# CopterControl_3D.net
KiCad netlist of a schematic drawn in Altium Designer
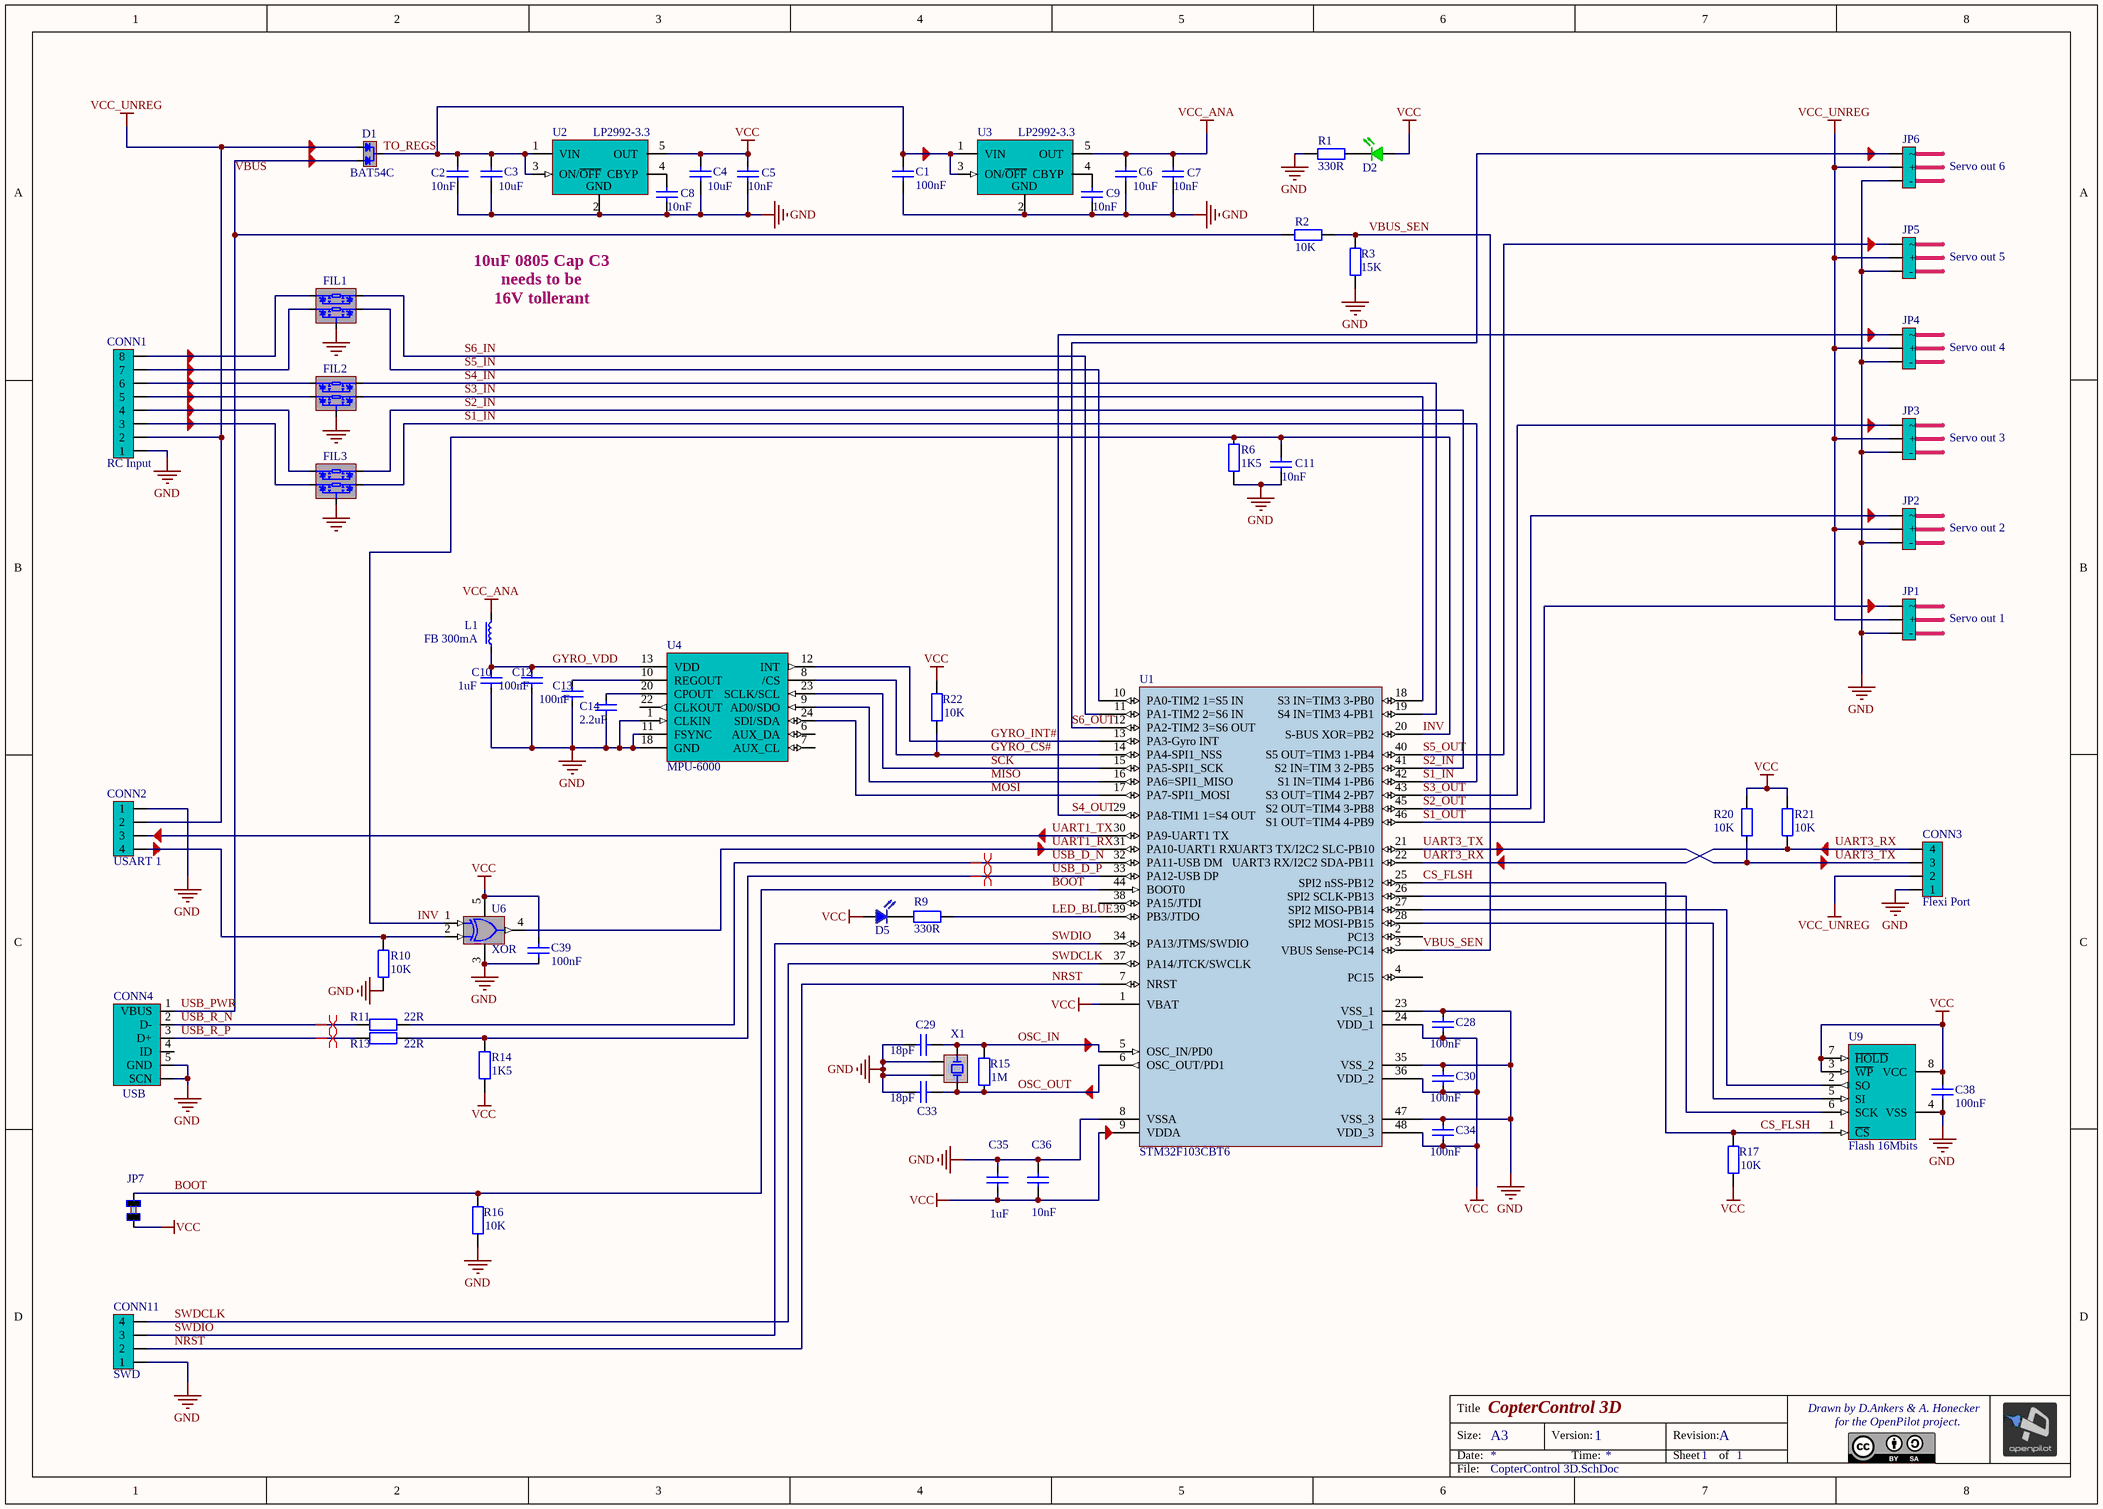
[diagram p0: CopterControl 3D.SchDoc]

(export (version "E")
  (design (tool "Eeschema 10.0.6"))
  (components
    (comp (ref "C1")
      (value "100nF")
      (footprint "CAP603N")
      (description "Capacitor SMD")
      (fields (field (name "Comment") "Cap603") (field (name "PUBLISHER") "The OpenPilot Project"))
      (libsource (lib "OpenPilot") (part "Cap603"))
    )
    (comp (ref "C2")
      (value "10nF")
      (footprint "CAP603L")
      (description "Capacitor SMD")
      (fields (field (name "Comment") "Cap603") (field (name "PUBLISHER") "The OpenPilot Project"))
      (libsource (lib "OpenPilot") (part "Cap603"))
    )
    (comp (ref "C3")
      (value "10uF")
      (footprint "CAP805L")
      (description "Capacitor SMD")
      (fields (field (name "Comment") "Cap805") (field (name "PUBLISHER") "The OpenPilot Project"))
      (libsource (lib "OpenPilot") (part "Cap805"))
    )
    (comp (ref "C4")
      (value "10uF")
      (footprint "CAP805L")
      (description "Capacitor SMD")
      (fields (field (name "Comment") "Cap805") (field (name "PUBLISHER") "The OpenPilot Project"))
      (libsource (lib "OpenPilot") (part "Cap805"))
    )
    (comp (ref "C5")
      (value "10nF")
      (footprint "CAP603N")
      (description "Capacitor SMD")
      (fields (field (name "Comment") "Cap603") (field (name "PUBLISHER") "The OpenPilot Project"))
      (libsource (lib "OpenPilot") (part "Cap603"))
    )
    (comp (ref "C6")
      (value "10uF")
      (footprint "CAP805L")
      (description "Capacitor SMD")
      (fields (field (name "Comment") "Cap805") (field (name "PUBLISHER") "The OpenPilot Project"))
      (libsource (lib "OpenPilot") (part "Cap805"))
    )
    (comp (ref "C7")
      (value "10nF")
      (footprint "CAP603N")
      (description "Capacitor SMD")
      (fields (field (name "Comment") "Cap603") (field (name "PUBLISHER") "The OpenPilot Project"))
      (libsource (lib "OpenPilot") (part "Cap603"))
    )
    (comp (ref "C8")
      (value "10nF")
      (footprint "CAP603N")
      (description "Capacitor SMD")
      (fields (field (name "Comment") "Cap603") (field (name "PUBLISHER") "The OpenPilot Project"))
      (libsource (lib "OpenPilot") (part "Cap603"))
    )
    (comp (ref "C9")
      (value "10nF")
      (footprint "CAP603N")
      (description "Capacitor SMD")
      (fields (field (name "Comment") "Cap603") (field (name "PUBLISHER") "The OpenPilot Project"))
      (libsource (lib "OpenPilot") (part "Cap603"))
    )
    (comp (ref "C10")
      (value "1uF")
      (footprint "CAP603L")
      (description "Capacitor SMD")
      (fields (field (name "Comment") "Cap603") (field (name "PUBLISHER") "The OpenPilot Project"))
      (libsource (lib "") (part "Cap603_1"))
    )
    (comp (ref "C11")
      (value "10nF")
      (footprint "CAP603N")
      (description "Capacitor SMD")
      (fields (field (name "Comment") "Cap603") (field (name "PUBLISHER") "The OpenPilot Project"))
      (libsource (lib "OpenPilot") (part "Cap603"))
    )
    (comp (ref "C12")
      (value "100nF")
      (footprint "CAP603L")
      (description "Capacitor SMD")
      (fields (field (name "Comment") "Cap603") (field (name "PUBLISHER") "The OpenPilot Project"))
      (libsource (lib "") (part "Cap603_1"))
    )
    (comp (ref "C13")
      (value "100nF")
      (footprint "CAP603L")
      (description "Capacitor SMD")
      (fields (field (name "Comment") "Cap603") (field (name "PUBLISHER") "The OpenPilot Project"))
      (libsource (lib "") (part "Cap603_1"))
    )
    (comp (ref "C14")
      (value "2.2uF")
      (footprint "CAP603L")
      (description "Capacitor SMD")
      (fields (field (name "Comment") "Cap603") (field (name "PUBLISHER") "The OpenPilot Project"))
      (libsource (lib "") (part "Cap603_1"))
    )
    (comp (ref "C28")
      (value "100nF")
      (footprint "CAP603N")
      (description "Capacitor SMD")
      (fields (field (name "Comment") "Cap603") (field (name "PUBLISHER") "The OpenPilot Project"))
      (libsource (lib "") (part "Cap603_1"))
    )
    (comp (ref "C29")
      (value "18pF")
      (footprint "CAP603N")
      (description "Capacitor SMD")
      (fields (field (name "Comment") "Cap603") (field (name "PUBLISHER") "The OpenPilot Project"))
      (libsource (lib "OpenPilot") (part "Cap603"))
    )
    (comp (ref "C30")
      (value "100nF")
      (footprint "CAP603N")
      (description "Capacitor SMD")
      (fields (field (name "Comment") "Cap603") (field (name "PUBLISHER") "The OpenPilot Project"))
      (libsource (lib "") (part "Cap603_1"))
    )
    (comp (ref "C33")
      (value "18pF")
      (footprint "CAP603N")
      (description "Capacitor SMD")
      (fields (field (name "Comment") "Cap603") (field (name "PUBLISHER") "The OpenPilot Project"))
      (libsource (lib "OpenPilot") (part "Cap603"))
    )
    (comp (ref "C34")
      (value "100nF")
      (footprint "CAP603N")
      (description "Capacitor SMD")
      (fields (field (name "Comment") "Cap603") (field (name "PUBLISHER") "The OpenPilot Project"))
      (libsource (lib "") (part "Cap603_1"))
    )
    (comp (ref "C35")
      (value "1uF")
      (footprint "CAP603L")
      (description "Capacitor SMD")
      (fields (field (name "Comment") "Cap603") (field (name "PUBLISHER") "The OpenPilot Project"))
      (libsource (lib "") (part "Cap603_1"))
    )
    (comp (ref "C36")
      (value "10nF")
      (footprint "CAP603N")
      (description "Capacitor SMD")
      (fields (field (name "Comment") "Cap603") (field (name "PUBLISHER") "The OpenPilot Project"))
      (libsource (lib "OpenPilot") (part "Cap603"))
    )
    (comp (ref "C38")
      (value "100nF")
      (footprint "CAP603N")
      (description "Capacitor SMD")
      (fields (field (name "Comment") "Cap603") (field (name "PUBLISHER") "The OpenPilot Project"))
      (libsource (lib "OpenPilot") (part "Cap603"))
    )
    (comp (ref "C39")
      (value "100nF")
      (footprint "CAP603N")
      (description "Capacitor SMD")
      (fields (field (name "Comment") "Cap603") (field (name "PUBLISHER") "The OpenPilot Project"))
      (libsource (lib "") (part "Cap603_1"))
    )
    (comp (ref "CONN1")
      (value "RC Input")
      (footprint "JST SH 8 Pin Side Entry")
      (description "JST-SH 8-pin Side Entry Socket")
      (fields (field (name "MANUFACTURER") "Generic Components"))
      (libsource (lib "OpenPilot") (part "JST-SH 8-pin Side Entry Socket"))
    )
    (comp (ref "CONN2")
      (value "USART 1")
      (footprint "JST SH 4 Pin Side Entry")
      (description "JST-SH 4-pin Side Entry Socket")
      (fields (field (name "MANUFACTURER") "Generic Components"))
      (libsource (lib "") (part "JST-SH 4-pin Side Entry Socket_2"))
    )
    (comp (ref "CONN3")
      (value "Flexi Port")
      (footprint "JST SH 4 Pin Side Entry")
      (description "JST-SH 4-pin Side Entry Socket")
      (fields (field (name "MANUFACTURER") "Generic Components"))
      (libsource (lib "OpenPilot") (part "JST-SH 4-pin Side Entry Socket"))
    )
    (comp (ref "CONN4")
      (value "USB")
      (footprint "USB SMD")
      (description "USB Type-B SMT Socket")
      (libsource (lib "OpenPilot") (part "USB_SMT_B"))
    )
    (comp (ref "CONN11")
      (value "SWD")
      (footprint "JST SH 4 Pin Side Entry")
      (description "JST-SH 4-pin Side Entry Socket")
      (fields (field (name "MANUFACTURER") "Generic Components"))
      (libsource (lib "") (part "JST-SH 4-pin Side Entry Socket_1"))
    )
    (comp (ref "D1")
      (value "BAT54C")
      (footprint "SOT23-3N")
      (description "Dual Diode Command Cathode")
      (libsource (lib "OpenPilot") (part "BAT54C"))
    )
    (comp (ref "D2")
      (value "Green")
      (footprint "LED603N")
      (description "Green 603 LED")
      (libsource (lib "OpenPilot") (part "LED 603 Gr"))
    )
    (comp (ref "D5")
      (value "Blue")
      (footprint "LED603N")
      (description "Blue 603 LED")
      (libsource (lib "OpenPilot") (part "LED 603 Bl"))
    )
    (comp (ref "FIL1")
      (value "IP4256CZ5-W,115")
      (footprint "SOT-665")
      (description "IP4256CZ5-W,115 2 channel, 100R, 30pF, RF ESD Filter")
      (fields
        (field (name "MANUFACTURER") "Generic Components")
        (field (name "PUBLISHER") "The OpenPilot Project")
      )
      (libsource (lib "OpenPilot") (part "RF Filter 100R 30pF"))
    )
    (comp (ref "FIL2")
      (value "IP4256CZ5-W,115")
      (footprint "SOT-665")
      (description "IP4256CZ5-W,115 2 channel, 100R, 30pF, RF ESD Filter")
      (fields
        (field (name "MANUFACTURER") "Generic Components")
        (field (name "PUBLISHER") "The OpenPilot Project")
      )
      (libsource (lib "OpenPilot") (part "RF Filter 100R 30pF"))
    )
    (comp (ref "FIL3")
      (value "IP4256CZ5-W,115")
      (footprint "SOT-665")
      (description "IP4256CZ5-W,115 2 channel, 100R, 30pF, RF ESD Filter")
      (fields
        (field (name "MANUFACTURER") "Generic Components")
        (field (name "PUBLISHER") "The OpenPilot Project")
      )
      (libsource (lib "OpenPilot") (part "RF Filter 100R 30pF"))
    )
    (comp (ref "JP1")
      (value "Servo out 1")
      (footprint "SIP3 - 0.1")
      (description "Header, 3-Pin, 0.1\"")
      (fields (field (name "MANUFACTURER") "Generic Components"))
      (libsource (lib "OpenPilot") (part "Hdr 3 Pin 0.1"))
    )
    (comp (ref "JP2")
      (value "Servo out 2")
      (footprint "SIP3 - 0.1")
      (description "Header, 3-Pin, 0.1\"")
      (fields (field (name "MANUFACTURER") "Generic Components"))
      (libsource (lib "OpenPilot") (part "Hdr 3 Pin 0.1"))
    )
    (comp (ref "JP3")
      (value "Servo out 3")
      (footprint "SIP3 - 0.1")
      (description "Header, 3-Pin, 0.1\"")
      (fields (field (name "MANUFACTURER") "Generic Components"))
      (libsource (lib "OpenPilot") (part "Hdr 3 Pin 0.1"))
    )
    (comp (ref "JP4")
      (value "Servo out 4")
      (footprint "SIP3 - 0.1")
      (description "Header, 3-Pin, 0.1\"")
      (fields (field (name "MANUFACTURER") "Generic Components"))
      (libsource (lib "OpenPilot") (part "Hdr 3 Pin 0.1"))
    )
    (comp (ref "JP5")
      (value "Servo out 5")
      (footprint "SIP3 - 0.1")
      (description "Header, 3-Pin, 0.1\"")
      (fields (field (name "MANUFACTURER") "Generic Components"))
      (libsource (lib "OpenPilot") (part "Hdr 3 Pin 0.1"))
    )
    (comp (ref "JP6")
      (value "Servo out 6")
      (footprint "SIP3 - 0.1")
      (description "Header, 3-Pin, 0.1\"")
      (fields (field (name "MANUFACTURER") "Generic Components"))
      (libsource (lib "OpenPilot") (part "Hdr 3 Pin 0.1"))
    )
    (comp (ref "JP7")
      (value "2 PAD Touch JMP")
      (footprint "TOUCH JMP 2PAD")
      (description "2 Pad Touch Jumper")
      (fields (field (name "PUBLISHER") "The OpenPilot Project"))
      (libsource (lib "OpenPilot") (part "2 PAD Touch JMP"))
    )
    (comp (ref "L1")
      (value "FB 300mA")
      (footprint "IND603N")
      (description "Ferrite Bead 300mA")
      (fields (field (name "MANUFACTURER") "Generic Components"))
      (libsource (lib "OpenPilot") (part "FerriteBead_300mA"))
    )
    (comp (ref "R1")
      (value "330R")
      (footprint "RES603N")
      (description "Resistor SMD")
      (fields (field (name "Comment") "Res603") (field (name "PUBLISHER") "The OpenPilot Project"))
      (libsource (lib "") (part "Res603_1"))
    )
    (comp (ref "R2")
      (value "10K")
      (footprint "RES603N")
      (description "Resistor SMD")
      (fields (field (name "Comment") "Res603") (field (name "PUBLISHER") "The OpenPilot Project"))
      (libsource (lib "") (part "Res603_1"))
    )
    (comp (ref "R3")
      (value "15K")
      (footprint "RES603N")
      (description "Resistor SMD")
      (fields (field (name "Comment") "Res603") (field (name "PUBLISHER") "The OpenPilot Project"))
      (libsource (lib "OpenPilot") (part "Res603"))
    )
    (comp (ref "R6")
      (value "1K5")
      (footprint "RES603N")
      (description "Resistor SMD")
      (fields (field (name "Comment") "Res603") (field (name "PUBLISHER") "The OpenPilot Project"))
      (libsource (lib "") (part "Res603_4"))
    )
    (comp (ref "R9")
      (value "330R")
      (footprint "RES603N")
      (description "Resistor SMD")
      (fields (field (name "Comment") "Res603") (field (name "PUBLISHER") "The OpenPilot Project"))
      (libsource (lib "") (part "Res603_1"))
    )
    (comp (ref "R10")
      (value "10K")
      (footprint "RES603N")
      (description "Resistor SMD")
      (fields (field (name "Comment") "Res603") (field (name "PUBLISHER") "The OpenPilot Project"))
      (libsource (lib "OpenPilot") (part "Res603"))
    )
    (comp (ref "R11")
      (value "22R")
      (footprint "RES603N")
      (description "Resistor SMD")
      (fields (field (name "Comment") "Res603") (field (name "PUBLISHER") "The OpenPilot Project"))
      (libsource (lib "") (part "Res603_2"))
    )
    (comp (ref "R13")
      (value "22R")
      (footprint "RES603N")
      (description "Resistor SMD")
      (fields (field (name "Comment") "Res603") (field (name "PUBLISHER") "The OpenPilot Project"))
      (libsource (lib "") (part "Res603_2"))
    )
    (comp (ref "R14")
      (value "1K5")
      (footprint "RES603N")
      (description "Resistor SMD")
      (fields (field (name "Comment") "Res603") (field (name "PUBLISHER") "The OpenPilot Project"))
      (libsource (lib "OpenPilot") (part "Res603"))
    )
    (comp (ref "R15")
      (value "1M")
      (footprint "RES603N")
      (description "Resistor SMD")
      (fields (field (name "Comment") "Res603") (field (name "PUBLISHER") "The OpenPilot Project"))
      (libsource (lib "") (part "Res603_3"))
    )
    (comp (ref "R16")
      (value "10K")
      (footprint "RES603N")
      (description "Resistor SMD")
      (fields (field (name "Comment") "Res603") (field (name "PUBLISHER") "The OpenPilot Project"))
      (libsource (lib "OpenPilot") (part "Res603"))
    )
    (comp (ref "R17")
      (value "10K")
      (footprint "RES603N")
      (description "Resistor SMD")
      (fields (field (name "Comment") "Res603") (field (name "PUBLISHER") "The OpenPilot Project"))
      (libsource (lib "OpenPilot") (part "Res603"))
    )
    (comp (ref "R20")
      (value "10K")
      (footprint "RES603N")
      (description "Resistor SMD")
      (fields (field (name "Comment") "Res603") (field (name "PUBLISHER") "The OpenPilot Project"))
      (libsource (lib "") (part "Res603_3"))
    )
    (comp (ref "R21")
      (value "10K")
      (footprint "RES603N")
      (description "Resistor SMD")
      (fields (field (name "Comment") "Res603") (field (name "PUBLISHER") "The OpenPilot Project"))
      (libsource (lib "OpenPilot") (part "Res603"))
    )
    (comp (ref "R22")
      (value "10K")
      (footprint "RES603N")
      (description "Resistor SMD")
      (fields (field (name "Comment") "Res603") (field (name "PUBLISHER") "The OpenPilot Project"))
      (libsource (lib "OpenPilot") (part "Res603"))
    )
    (comp (ref "U1")
      (value "STM32F103CBT6")
      (footprint "STM32 48 Lead")
      (description "STM32 ARM-based 32-bit MCU with 128 Kbytes Flash, 48-pin LQFP, Industrial Temperature")
      (fields (field (name "PUBLISHER") "Altium Limited"))
      (libsource (lib "OpenPilot") (part "STM32F103CBT6"))
    )
    (comp (ref "U2")
      (value "LP2992-3.3")
      (footprint "SOT23-5L")
      (description "3.3V 250mA LDO Regulator")
      (fields
        (field (name "MANUFACTURER") "National Semiconductor")
        (field (name "MANUFACTURER PART NUMBER") "LP2992AIM5-3.3/NOPB")
      )
      (libsource (lib "OpenPilot") (part "LP2985-3.3"))
    )
    (comp (ref "U3")
      (value "LP2992-3.3")
      (footprint "SOT23-5L")
      (description "3.3V 250mA LDO Regulator")
      (fields
        (field (name "MANUFACTURER") "National Semiconductor")
        (field (name "MANUFACTURER PART NUMBER") "LP2992AIM5-3.3/NOPB")
      )
      (libsource (lib "OpenPilot") (part "LP2985-3.3"))
    )
    (comp (ref "U4")
      (value "MPU-6000")
      (footprint "IMU-3000")
      (description "Invensense MPU-3/6000,  3-axis Gyros & Accel on 6000")
      (fields (field (name "MANUFACTURER") "Invensense") (field (name "PUBLISHER") "The OpenPilot Project"))
      (libsource (lib "OpenPilot") (part "MPU-3/6000"))
    )
    (comp (ref "U6")
      (value "XOR")
      (footprint "DCK-5")
      (description "XOR Gate SN74LVC1G86DCKR")
      (libsource (lib "OpenPilot") (part "XOR SN74LVC1G86DCKR"))
    )
    (comp (ref "U9")
      (value "Flash 16Mbits")
      (footprint "SOIC8_N")
      (description "16Mbit SPI Flash Memory")
      (fields (field (name "PUBLISHER") "The OpenPilot Project"))
      (libsource (lib "OpenPilot") (part "Flash 16Mb 75MHZ 8SOIC"))
    )
    (comp (ref "X1")
      (value "8MHz")
      (footprint "XTAL ACT530SMX-4 Series")
      (description "Surface Mount Quartz Crystal, Digikey 535-9720-1-ND")
      (libsource (lib "OpenPilot") (part "XTAL ACT530SMX-4"))
    )
  )
  (nets
    (net (code "1") (name "/BOOT") (class "Default")
      (node (ref "JP7") (pin "1") (pinfunction "1_1") (pintype "passive"))
      (node (ref "R16") (pin "2") (pinfunction "2_2") (pintype "passive"))
      (node (ref "U1") (pin "44") (pinfunction "BOOT0_44") (pintype "input"))
    )
    (net (code "2") (name "/CS_FLSH") (class "Default")
      (node (ref "R17") (pin "2") (pinfunction "2_2") (pintype "passive"))
      (node (ref "U1") (pin "25") (pinfunction "SPI2_nSS-PB12_25") (pintype "bidirectional"))
      (node (ref "U9") (pin "1") (pinfunction "~{CS}_1") (pintype "input"))
    )
    (net (code "3") (name "/GYRO_CS#") (class "Default")
      (node (ref "R22") (pin "1") (pinfunction "1_1") (pintype "passive"))
      (node (ref "U1") (pin "14") (pinfunction "PA4-SPI1_NSS_14") (pintype "bidirectional"))
      (node (ref "U4") (pin "8") (pinfunction "/CS_8") (pintype "passive"))
    )
    (net (code "4") (name "/GYRO_INT#") (class "Default")
      (node (ref "U1") (pin "13") (pinfunction "PA3-Gyro_INT_13") (pintype "bidirectional"))
      (node (ref "U4") (pin "12") (pinfunction "INT_12") (pintype "output"))
    )
    (net (code "5") (name "/GYRO_VDD") (class "Default")
      (node (ref "C10") (pin "1") (pinfunction "1_1") (pintype "passive"))
      (node (ref "C12") (pin "1") (pinfunction "1_1") (pintype "passive"))
      (node (ref "L1") (pin "1") (pinfunction "1_1") (pintype "passive"))
      (node (ref "U4") (pin "13") (pinfunction "VDD_13") (pintype "power_in"))
    )
    (net (code "6") (name "/INV") (class "Default")
      (node (ref "C11") (pin "1") (pinfunction "1_1") (pintype "passive"))
      (node (ref "R6") (pin "2") (pinfunction "2_2") (pintype "passive"))
      (node (ref "U1") (pin "20") (pinfunction "S-BUS_XOR=PB2_20") (pintype "bidirectional"))
      (node (ref "U6") (pin "1") (pinfunction "A_1") (pintype "input"))
    )
    (net (code "7") (name "/LED_BLUE") (class "Default")
      (node (ref "R9") (pin "2") (pinfunction "2_2") (pintype "passive"))
      (node (ref "U1") (pin "39") (pinfunction "PB3/JTDO_39") (pintype "bidirectional"))
    )
    (net (code "8") (name "/MISO") (class "Default")
      (node (ref "U1") (pin "16") (pinfunction "PA6=SPI1_MISO_16") (pintype "bidirectional"))
      (node (ref "U4") (pin "9") (pinfunction "AD0/SDO_9") (pintype "input"))
    )
    (net (code "9") (name "/MOSI") (class "Default")
      (node (ref "U1") (pin "17") (pinfunction "PA7-SPI1_MOSI_17") (pintype "bidirectional"))
      (node (ref "U4") (pin "24") (pinfunction "SDI/SDA_24") (pintype "bidirectional"))
    )
    (net (code "10") (name "/NRST") (class "Default")
      (node (ref "CONN11") (pin "2") (pinfunction "2_2") (pintype "passive"))
      (node (ref "U1") (pin "7") (pinfunction "NRST_7") (pintype "bidirectional"))
    )
    (net (code "11") (name "/OSC_IN") (class "Default")
      (node (ref "C29") (pin "2") (pinfunction "2_2") (pintype "passive"))
      (node (ref "R15") (pin "2") (pinfunction "2_2") (pintype "passive"))
      (node (ref "U1") (pin "5") (pinfunction "OSC_IN/PD0_5") (pintype "input"))
      (node (ref "X1") (pin "3") (pinfunction "3_3") (pintype "passive"))
    )
    (net (code "12") (name "/OSC_OUT") (class "Default")
      (node (ref "C33") (pin "2") (pinfunction "2_2") (pintype "passive"))
      (node (ref "R15") (pin "1") (pinfunction "1_1") (pintype "passive"))
      (node (ref "U1") (pin "6") (pinfunction "OSC_OUT/PD1_6") (pintype "output"))
      (node (ref "X1") (pin "1") (pinfunction "1_1") (pintype "passive"))
    )
    (net (code "13") (name "/S1_IN") (class "Default")
      (node (ref "FIL3") (pin "5") (pinfunction "5_5") (pintype "passive"))
      (node (ref "U1") (pin "42") (pinfunction "S1_IN=TIM4_1-PB6_42") (pintype "bidirectional"))
    )
    (net (code "14") (name "/S1_OUT") (class "Default")
      (node (ref "JP1") (pin "1") (pinfunction "~_1") (pintype "passive"))
      (node (ref "U1") (pin "46") (pinfunction "S1_OUT=TIM4_4-PB9_46") (pintype "bidirectional"))
    )
    (net (code "15") (name "/S2_IN") (class "Default")
      (node (ref "FIL3") (pin "4") (pinfunction "4_4") (pintype "passive"))
      (node (ref "U1") (pin "41") (pinfunction "S2_IN=TIM_3_2-PB5_41") (pintype "bidirectional"))
    )
    (net (code "16") (name "/S2_OUT") (class "Default")
      (node (ref "JP2") (pin "1") (pinfunction "~_1") (pintype "passive"))
      (node (ref "U1") (pin "45") (pinfunction "S2_OUT=TIM4_3-PB8_45") (pintype "bidirectional"))
    )
    (net (code "17") (name "/S3_IN") (class "Default")
      (node (ref "FIL2") (pin "5") (pinfunction "5_5") (pintype "passive"))
      (node (ref "U1") (pin "18") (pinfunction "S3_IN=TIM3_3-PB0_18") (pintype "bidirectional"))
    )
    (net (code "18") (name "/S3_OUT") (class "Default")
      (node (ref "JP3") (pin "1") (pinfunction "~_1") (pintype "passive"))
      (node (ref "U1") (pin "43") (pinfunction "S3_OUT=TIM4_2-PB7_43") (pintype "bidirectional"))
    )
    (net (code "19") (name "/S4_IN") (class "Default")
      (node (ref "FIL2") (pin "4") (pinfunction "4_4") (pintype "passive"))
      (node (ref "U1") (pin "19") (pinfunction "S4_IN=TIM3_4-PB1_19") (pintype "bidirectional"))
    )
    (net (code "20") (name "/S4_OUT") (class "Default")
      (node (ref "JP4") (pin "1") (pinfunction "~_1") (pintype "passive"))
      (node (ref "U1") (pin "29") (pinfunction "PA8-TIM1_1=S4_OUT_29") (pintype "bidirectional"))
    )
    (net (code "21") (name "/S5_IN") (class "Default")
      (node (ref "FIL1") (pin "5") (pinfunction "5_5") (pintype "passive"))
      (node (ref "U1") (pin "10") (pinfunction "PA0-TIM2_1=S5_IN_10") (pintype "bidirectional"))
    )
    (net (code "22") (name "/S5_OUT") (class "Default")
      (node (ref "JP5") (pin "1") (pinfunction "~_1") (pintype "passive"))
      (node (ref "U1") (pin "40") (pinfunction "S5_OUT=TIM3_1-PB4_40") (pintype "bidirectional"))
    )
    (net (code "23") (name "/S6_IN") (class "Default")
      (node (ref "FIL1") (pin "4") (pinfunction "4_4") (pintype "passive"))
      (node (ref "U1") (pin "11") (pinfunction "PA1-TIM2_2=S6_IN_11") (pintype "bidirectional"))
    )
    (net (code "24") (name "/S6_OUT") (class "Default")
      (node (ref "JP6") (pin "1") (pinfunction "~_1") (pintype "passive"))
      (node (ref "U1") (pin "12") (pinfunction "PA2-TIM2_3=S6_OUT_12") (pintype "bidirectional"))
    )
    (net (code "25") (name "/SCK") (class "Default")
      (node (ref "U1") (pin "15") (pinfunction "PA5-SPI1_SCK_15") (pintype "bidirectional"))
      (node (ref "U4") (pin "23") (pinfunction "SCLK/SCL_23") (pintype "input"))
    )
    (net (code "26") (name "/SWDCLK") (class "Default")
      (node (ref "CONN11") (pin "4") (pinfunction "4_4") (pintype "passive"))
      (node (ref "U1") (pin "37") (pinfunction "PA14/JTCK/SWCLK_37") (pintype "bidirectional"))
    )
    (net (code "27") (name "/SWDIO") (class "Default")
      (node (ref "CONN11") (pin "3") (pinfunction "3_3") (pintype "passive"))
      (node (ref "U1") (pin "34") (pinfunction "PA13/JTMS/SWDIO_34") (pintype "bidirectional"))
    )
    (net (code "28") (name "/TO_REGS") (class "Default")
      (node (ref "C1") (pin "1") (pinfunction "1_1") (pintype "passive"))
      (node (ref "C2") (pin "1") (pinfunction "1_1") (pintype "passive"))
      (node (ref "C3") (pin "1") (pinfunction "1_1") (pintype "passive"))
      (node (ref "D1") (pin "3") (pinfunction "COM_3") (pintype "passive"))
      (node (ref "U2") (pin "1") (pinfunction "VIN_1") (pintype "power_in"))
      (node (ref "U2") (pin "3") (pinfunction "ON/~{OFF}_3") (pintype "input"))
      (node (ref "U3") (pin "1") (pinfunction "VIN_1") (pintype "power_in"))
      (node (ref "U3") (pin "3") (pinfunction "ON/~{OFF}_3") (pintype "input"))
    )
    (net (code "29") (name "/UART1_RX") (class "Default")
      (node (ref "U1") (pin "31") (pinfunction "PA10-UART1_RX_31") (pintype "bidirectional"))
      (node (ref "U6") (pin "4") (pinfunction "Y_4") (pintype "output"))
    )
    (net (code "30") (name "/UART1_TX") (class "Default")
      (node (ref "CONN2") (pin "3") (pinfunction "3_3") (pintype "passive"))
      (node (ref "U1") (pin "30") (pinfunction "PA9-UART1_TX_30") (pintype "bidirectional"))
    )
    (net (code "31") (name "/UART3_RX") (class "Default")
      (node (ref "CONN3") (pin "4") (pinfunction "4_4") (pintype "passive"))
      (node (ref "R21") (pin "1") (pinfunction "1_1") (pintype "passive"))
      (node (ref "U1") (pin "22") (pinfunction "UART3_RX/I2C2_SDA-PB11_22") (pintype "bidirectional"))
    )
    (net (code "32") (name "/UART3_TX") (class "Default")
      (node (ref "CONN3") (pin "3") (pinfunction "3_3") (pintype "passive"))
      (node (ref "R20") (pin "1") (pinfunction "1_1") (pintype "passive"))
      (node (ref "U1") (pin "21") (pinfunction "UART3_TX/I2C2_SLC-PB10_21") (pintype "bidirectional"))
    )
    (net (code "33") (name "/USB_D_N") (class "Default")
      (node (ref "R11") (pin "1") (pinfunction "1_1") (pintype "passive"))
      (node (ref "U1") (pin "32") (pinfunction "PA11-USB_DM_32") (pintype "bidirectional"))
    )
    (net (code "34") (name "/USB_D_P") (class "Default")
      (node (ref "R13") (pin "1") (pinfunction "1_1") (pintype "passive"))
      (node (ref "R14") (pin "2") (pinfunction "2_2") (pintype "passive"))
      (node (ref "U1") (pin "33") (pinfunction "PA12-USB_DP_33") (pintype "bidirectional"))
    )
    (net (code "35") (name "/USB_PWR") (class "Default")
      (node (ref "CONN4") (pin "1") (pinfunction "VBUS_1") (pintype "passive"))
      (node (ref "D1") (pin "1") (pinfunction "A1_1") (pintype "passive"))
      (node (ref "R2") (pin "1") (pinfunction "1_1") (pintype "passive"))
    )
    (net (code "36") (name "/USB_R_N") (class "Default")
      (node (ref "CONN4") (pin "2") (pinfunction "D-_2") (pintype "passive"))
      (node (ref "R11") (pin "2") (pinfunction "2_2") (pintype "passive"))
    )
    (net (code "37") (name "/USB_R_P") (class "Default")
      (node (ref "CONN4") (pin "3") (pinfunction "D+_3") (pintype "passive"))
      (node (ref "R13") (pin "2") (pinfunction "2_2") (pintype "passive"))
    )
    (net (code "38") (name "/VBUS_SEN") (class "Default")
      (node (ref "R2") (pin "2") (pinfunction "2_2") (pintype "passive"))
      (node (ref "R3") (pin "2") (pinfunction "2_2") (pintype "passive"))
      (node (ref "U1") (pin "3") (pinfunction "VBUS_Sense-PC14_3") (pintype "bidirectional"))
    )
    (net (code "39") (name "GND") (class "Default")
      (node (ref "C1") (pin "2") (pinfunction "2_2") (pintype "passive"))
      (node (ref "C10") (pin "2") (pinfunction "2_2") (pintype "passive"))
      (node (ref "C11") (pin "2") (pinfunction "2_2") (pintype "passive"))
      (node (ref "C12") (pin "2") (pinfunction "2_2") (pintype "passive"))
      (node (ref "C13") (pin "2") (pinfunction "2_2") (pintype "passive"))
      (node (ref "C14") (pin "1") (pinfunction "1_1") (pintype "passive"))
      (node (ref "C2") (pin "2") (pinfunction "2_2") (pintype "passive"))
      (node (ref "C28") (pin "1") (pinfunction "1_1") (pintype "passive"))
      (node (ref "C29") (pin "1") (pinfunction "1_1") (pintype "passive"))
      (node (ref "C3") (pin "2") (pinfunction "2_2") (pintype "passive"))
      (node (ref "C30") (pin "1") (pinfunction "1_1") (pintype "passive"))
      (node (ref "C33") (pin "1") (pinfunction "1_1") (pintype "passive"))
      (node (ref "C34") (pin "1") (pinfunction "1_1") (pintype "passive"))
      (node (ref "C35") (pin "2") (pinfunction "2_2") (pintype "passive"))
      (node (ref "C36") (pin "1") (pinfunction "1_1") (pintype "passive"))
      (node (ref "C38") (pin "2") (pinfunction "2_2") (pintype "passive"))
      (node (ref "C39") (pin "2") (pinfunction "2_2") (pintype "passive"))
      (node (ref "C4") (pin "2") (pinfunction "2_2") (pintype "passive"))
      (node (ref "C5") (pin "2") (pinfunction "2_2") (pintype "passive"))
      (node (ref "C6") (pin "2") (pinfunction "2_2") (pintype "passive"))
      (node (ref "C7") (pin "2") (pinfunction "2_2") (pintype "passive"))
      (node (ref "C8") (pin "2") (pinfunction "2_2") (pintype "passive"))
      (node (ref "C9") (pin "2") (pinfunction "2_2") (pintype "passive"))
      (node (ref "CONN1") (pin "1") (pinfunction "1_1") (pintype "passive"))
      (node (ref "CONN11") (pin "1") (pinfunction "1_1") (pintype "passive"))
      (node (ref "CONN2") (pin "1") (pinfunction "1_1") (pintype "passive"))
      (node (ref "CONN3") (pin "1") (pinfunction "1_1") (pintype "passive"))
      (node (ref "CONN4") (pin "0") (pinfunction "SCN_0") (pintype "passive"))
      (node (ref "CONN4") (pin "5") (pinfunction "GND_5") (pintype "passive"))
      (node (ref "FIL1") (pin "2") (pinfunction "PAD_2") (pintype "passive"))
      (node (ref "FIL2") (pin "2") (pinfunction "PAD_2") (pintype "passive"))
      (node (ref "FIL3") (pin "2") (pinfunction "PAD_2") (pintype "passive"))
      (node (ref "JP1") (pin "3") (pinfunction "-_3") (pintype "passive"))
      (node (ref "JP2") (pin "3") (pinfunction "-_3") (pintype "passive"))
      (node (ref "JP3") (pin "3") (pinfunction "-_3") (pintype "passive"))
      (node (ref "JP4") (pin "3") (pinfunction "-_3") (pintype "passive"))
      (node (ref "JP5") (pin "3") (pinfunction "-_3") (pintype "passive"))
      (node (ref "JP6") (pin "3") (pinfunction "-_3") (pintype "passive"))
      (node (ref "R1") (pin "1") (pinfunction "1_1") (pintype "passive"))
      (node (ref "R10") (pin "1") (pinfunction "1_1") (pintype "passive"))
      (node (ref "R16") (pin "1") (pinfunction "1_1") (pintype "passive"))
      (node (ref "R3") (pin "1") (pinfunction "1_1") (pintype "passive"))
      (node (ref "R6") (pin "1") (pinfunction "1_1") (pintype "passive"))
      (node (ref "U1") (pin "23") (pinfunction "VSS_1_23") (pintype "power_in"))
      (node (ref "U1") (pin "35") (pinfunction "VSS_2_35") (pintype "power_in"))
      (node (ref "U1") (pin "47") (pinfunction "VSS_3_47") (pintype "power_in"))
      (node (ref "U1") (pin "8") (pinfunction "VSSA_8") (pintype "power_in"))
      (node (ref "U2") (pin "2") (pinfunction "GND_2") (pintype "power_in"))
      (node (ref "U3") (pin "2") (pinfunction "GND_2") (pintype "power_in"))
      (node (ref "U4") (pin "1") (pinfunction "CLKIN_1") (pintype "input"))
      (node (ref "U4") (pin "11") (pinfunction "FSYNC_11") (pintype "passive"))
      (node (ref "U4") (pin "18") (pinfunction "GND_18") (pintype "power_in"))
      (node (ref "U6") (pin "3") (pinfunction "GND_3") (pintype "power_in"))
      (node (ref "U9") (pin "4") (pinfunction "VSS_4") (pintype "power_in"))
      (node (ref "X1") (pin "2") (pinfunction "2_2") (pintype "passive"))
      (node (ref "X1") (pin "4") (pinfunction "4_4") (pintype "passive"))
    )
    (net (code "40") (name "Net-(CONN1-Pad3)") (class "Default")
      (node (ref "CONN1") (pin "3") (pinfunction "3_3") (pintype "passive"))
      (node (ref "FIL3") (pin "1") (pinfunction "1_1") (pintype "passive"))
    )
    (net (code "41") (name "Net-(CONN1-Pad4)") (class "Default")
      (node (ref "CONN1") (pin "4") (pinfunction "4_4") (pintype "passive"))
      (node (ref "FIL3") (pin "3") (pinfunction "3_3") (pintype "passive"))
    )
    (net (code "42") (name "Net-(CONN1-Pad5)") (class "Default")
      (node (ref "CONN1") (pin "5") (pinfunction "5_5") (pintype "passive"))
      (node (ref "FIL2") (pin "1") (pinfunction "1_1") (pintype "passive"))
    )
    (net (code "43") (name "Net-(CONN1-Pad6)") (class "Default")
      (node (ref "CONN1") (pin "6") (pinfunction "6_6") (pintype "passive"))
      (node (ref "FIL2") (pin "3") (pinfunction "3_3") (pintype "passive"))
    )
    (net (code "44") (name "Net-(CONN1-Pad7)") (class "Default")
      (node (ref "CONN1") (pin "7") (pinfunction "7_7") (pintype "passive"))
      (node (ref "FIL1") (pin "1") (pinfunction "1_1") (pintype "passive"))
    )
    (net (code "45") (name "Net-(CONN1-Pad8)") (class "Default")
      (node (ref "CONN1") (pin "8") (pinfunction "8_8") (pintype "passive"))
      (node (ref "FIL1") (pin "3") (pinfunction "3_3") (pintype "passive"))
    )
    (net (code "46") (name "Net-(D2-K)") (class "Default")
      (node (ref "D2") (pin "1") (pinfunction "K_1") (pintype "passive"))
      (node (ref "R1") (pin "2") (pinfunction "2_2") (pintype "passive"))
    )
    (net (code "47") (name "Net-(D5-K)") (class "Default")
      (node (ref "D5") (pin "1") (pinfunction "K_1") (pintype "passive"))
      (node (ref "R9") (pin "1") (pinfunction "1_1") (pintype "passive"))
    )
    (net (code "48") (name "Net-(U1-SPI2_MISO-PB14)") (class "Default")
      (node (ref "U1") (pin "27") (pinfunction "SPI2_MISO-PB14_27") (pintype "bidirectional"))
      (node (ref "U9") (pin "2") (pinfunction "SO_2") (pintype "output"))
    )
    (net (code "49") (name "Net-(U1-SPI2_MOSI-PB15)") (class "Default")
      (node (ref "U1") (pin "28") (pinfunction "SPI2_MOSI-PB15_28") (pintype "bidirectional"))
      (node (ref "U9") (pin "5") (pinfunction "SI_5") (pintype "input"))
    )
    (net (code "50") (name "Net-(U1-SPI2_SCLK-PB13)") (class "Default")
      (node (ref "U1") (pin "26") (pinfunction "SPI2_SCLK-PB13_26") (pintype "bidirectional"))
      (node (ref "U9") (pin "6") (pinfunction "SCK_6") (pintype "input"))
    )
    (net (code "51") (name "Net-(U2-CBYP)") (class "Default")
      (node (ref "C8") (pin "1") (pinfunction "1_1") (pintype "passive"))
      (node (ref "U2") (pin "4") (pinfunction "CBYP_4") (pintype "passive"))
    )
    (net (code "52") (name "Net-(U3-CBYP)") (class "Default")
      (node (ref "C9") (pin "1") (pinfunction "1_1") (pintype "passive"))
      (node (ref "U3") (pin "4") (pinfunction "CBYP_4") (pintype "passive"))
    )
    (net (code "53") (name "Net-(U4-CPOUT)") (class "Default")
      (node (ref "C14") (pin "2") (pinfunction "2_2") (pintype "passive"))
      (node (ref "U4") (pin "20") (pinfunction "CPOUT_20") (pintype "passive"))
    )
    (net (code "54") (name "Net-(U4-REGOUT)") (class "Default")
      (node (ref "C13") (pin "1") (pinfunction "1_1") (pintype "passive"))
      (node (ref "U4") (pin "10") (pinfunction "REGOUT_10") (pintype "passive"))
    )
    (net (code "55") (name "Net-(U6-B)") (class "Default")
      (node (ref "CONN2") (pin "4") (pinfunction "4_4") (pintype "passive"))
      (node (ref "R10") (pin "2") (pinfunction "2_2") (pintype "passive"))
      (node (ref "U6") (pin "2") (pinfunction "B_2") (pintype "input"))
    )
    (net (code "56") (name "VCC") (class "Default")
      (node (ref "C28") (pin "2") (pinfunction "2_2") (pintype "passive"))
      (node (ref "C30") (pin "2") (pinfunction "2_2") (pintype "passive"))
      (node (ref "C34") (pin "2") (pinfunction "2_2") (pintype "passive"))
      (node (ref "C35") (pin "1") (pinfunction "1_1") (pintype "passive"))
      (node (ref "C36") (pin "2") (pinfunction "2_2") (pintype "passive"))
      (node (ref "C38") (pin "1") (pinfunction "1_1") (pintype "passive"))
      (node (ref "C39") (pin "1") (pinfunction "1_1") (pintype "passive"))
      (node (ref "C4") (pin "1") (pinfunction "1_1") (pintype "passive"))
      (node (ref "C5") (pin "1") (pinfunction "1_1") (pintype "passive"))
      (node (ref "D2") (pin "2") (pinfunction "A_2") (pintype "passive"))
      (node (ref "D5") (pin "2") (pinfunction "A_2") (pintype "passive"))
      (node (ref "JP7") (pin "2") (pinfunction "2_2") (pintype "passive"))
      (node (ref "R14") (pin "1") (pinfunction "1_1") (pintype "passive"))
      (node (ref "R17") (pin "1") (pinfunction "1_1") (pintype "passive"))
      (node (ref "R20") (pin "2") (pinfunction "2_2") (pintype "passive"))
      (node (ref "R21") (pin "2") (pinfunction "2_2") (pintype "passive"))
      (node (ref "R22") (pin "2") (pinfunction "2_2") (pintype "passive"))
      (node (ref "U1") (pin "1") (pinfunction "VBAT_1") (pintype "power_in"))
      (node (ref "U1") (pin "24") (pinfunction "VDD_1_24") (pintype "power_in"))
      (node (ref "U1") (pin "36") (pinfunction "VDD_2_36") (pintype "power_in"))
      (node (ref "U1") (pin "48") (pinfunction "VDD_3_48") (pintype "power_in"))
      (node (ref "U1") (pin "9") (pinfunction "VDDA_9") (pintype "power_in"))
      (node (ref "U2") (pin "5") (pinfunction "OUT_5") (pintype "power_in"))
      (node (ref "U6") (pin "5") (pinfunction "VCC_5") (pintype "power_in"))
      (node (ref "U9") (pin "3") (pinfunction "~{WP}_3") (pintype "input"))
      (node (ref "U9") (pin "7") (pinfunction "~{HOLD}_7") (pintype "input"))
      (node (ref "U9") (pin "8") (pinfunction "VCC_8") (pintype "power_in"))
    )
    (net (code "57") (name "VCC_ANA") (class "Default")
      (node (ref "C6") (pin "1") (pinfunction "1_1") (pintype "passive"))
      (node (ref "C7") (pin "1") (pinfunction "1_1") (pintype "passive"))
      (node (ref "L1") (pin "2") (pinfunction "2_2") (pintype "passive"))
      (node (ref "U3") (pin "5") (pinfunction "OUT_5") (pintype "power_in"))
    )
    (net (code "58") (name "VCC_UNREG") (class "Default")
      (node (ref "CONN1") (pin "2") (pinfunction "2_2") (pintype "passive"))
      (node (ref "CONN2") (pin "2") (pinfunction "2_2") (pintype "passive"))
      (node (ref "CONN3") (pin "2") (pinfunction "2_2") (pintype "passive"))
      (node (ref "D1") (pin "2") (pinfunction "A2_2") (pintype "passive"))
      (node (ref "JP1") (pin "2") (pinfunction "+_2") (pintype "passive"))
      (node (ref "JP2") (pin "2") (pinfunction "+_2") (pintype "passive"))
      (node (ref "JP3") (pin "2") (pinfunction "+_2") (pintype "passive"))
      (node (ref "JP4") (pin "2") (pinfunction "+_2") (pintype "passive"))
      (node (ref "JP5") (pin "2") (pinfunction "+_2") (pintype "passive"))
      (node (ref "JP6") (pin "2") (pinfunction "+_2") (pintype "passive"))
    )
    (net (code "59") (name "unconnected-(CONN4-ID-Pad4)") (class "Default")
      (node (ref "CONN4") (pin "4") (pinfunction "ID_4") (pintype "passive"))
    )
    (net (code "60") (name "unconnected-(U1-PA15{slash}JTDI-Pad38)") (class "Default")
      (node (ref "U1") (pin "38") (pinfunction "PA15/JTDI_38") (pintype "bidirectional"))
    )
    (net (code "61") (name "unconnected-(U1-PC13-Pad2)") (class "Default")
      (node (ref "U1") (pin "2") (pinfunction "PC13_2") (pintype "bidirectional"))
    )
    (net (code "62") (name "unconnected-(U1-PC15-Pad4)") (class "Default")
      (node (ref "U1") (pin "4") (pinfunction "PC15_4") (pintype "bidirectional"))
    )
    (net (code "63") (name "unconnected-(U4-AUX_CL-Pad7)") (class "Default")
      (node (ref "U4") (pin "7") (pinfunction "AUX_CL_7") (pintype "bidirectional"))
    )
    (net (code "64") (name "unconnected-(U4-AUX_DA-Pad6)") (class "Default")
      (node (ref "U4") (pin "6") (pinfunction "AUX_DA_6") (pintype "bidirectional"))
    )
    (net (code "65") (name "unconnected-(U4-CLKOUT-Pad22)") (class "Default")
      (node (ref "U4") (pin "22") (pinfunction "CLKOUT_22") (pintype "output"))
    )
    (net (code "66") (name "unconnected-(U4-NC-Pad2)") (class "Default")
      (node (ref "U4") (pin "2") (pinfunction "NC_2") (pintype "tri_state"))
    )
    (net (code "67") (name "unconnected-(U4-NC-Pad3)") (class "Default")
      (node (ref "U4") (pin "3") (pinfunction "NC_3") (pintype "tri_state"))
    )
    (net (code "68") (name "unconnected-(U4-NC-Pad4)") (class "Default")
      (node (ref "U4") (pin "4") (pinfunction "NC_4") (pintype "tri_state"))
    )
    (net (code "69") (name "unconnected-(U4-NC-Pad5)") (class "Default")
      (node (ref "U4") (pin "5") (pinfunction "NC_5") (pintype "tri_state"))
    )
    (net (code "70") (name "unconnected-(U4-NC-Pad14)") (class "Default")
      (node (ref "U4") (pin "14") (pinfunction "NC_14") (pintype "bidirectional"))
    )
    (net (code "71") (name "unconnected-(U4-NC-Pad15)") (class "Default")
      (node (ref "U4") (pin "15") (pinfunction "NC_15") (pintype "tri_state"))
    )
    (net (code "72") (name "unconnected-(U4-NC-Pad16)") (class "Default")
      (node (ref "U4") (pin "16") (pinfunction "NC_16") (pintype "tri_state"))
    )
    (net (code "73") (name "unconnected-(U4-NC-Pad17)") (class "Default")
      (node (ref "U4") (pin "17") (pinfunction "NC_17") (pintype "tri_state"))
    )
    (net (code "74") (name "unconnected-(U4-RESV-Pad19)") (class "Default")
      (node (ref "U4") (pin "19") (pinfunction "RESV_19") (pintype "passive"))
    )
    (net (code "75") (name "unconnected-(U4-RESV-Pad21)") (class "Default")
      (node (ref "U4") (pin "21") (pinfunction "RESV_21") (pintype "passive"))
    )
  )
)
